# Power.net
KiCad netlist of a schematic drawn in Altium Designer
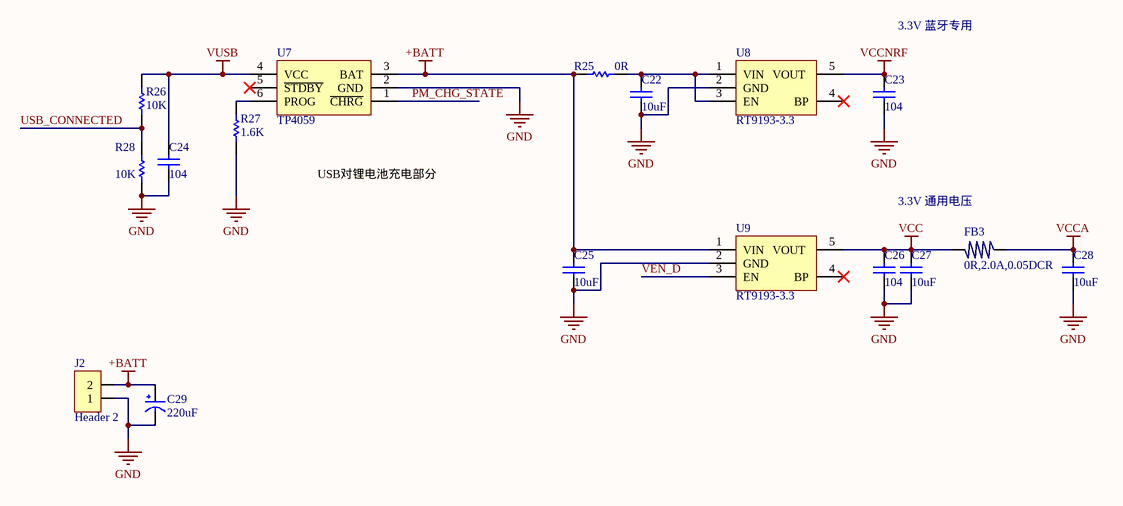
[diagram p0: Power.SchDoc]

(export (version "E")
  (design (tool "Eeschema 10.0.6"))
  (components
    (comp (ref "C22")
      (value "10uF")
      (footprint "C0603")
      (description "电容")
      (fields (field (name "PUBLISHER") "Altium Limited"))
      (libsource (lib "Devices") (part "C0603"))
    )
    (comp (ref "C23")
      (value "104")
      (footprint "C0603")
      (description "电容")
      (fields (field (name "PUBLISHER") "Altium Limited"))
      (libsource (lib "Devices") (part "C0603"))
    )
    (comp (ref "C24")
      (value "104")
      (footprint "C0603")
      (description "电容")
      (fields (field (name "PUBLISHER") "Altium Limited"))
      (libsource (lib "Devices") (part "C0603"))
    )
    (comp (ref "C25")
      (value "10uF")
      (footprint "C0603")
      (description "电容")
      (fields (field (name "PUBLISHER") "Altium Limited"))
      (libsource (lib "Devices") (part "C0603"))
    )
    (comp (ref "C26")
      (value "104")
      (footprint "C0603")
      (description "电容")
      (fields (field (name "PUBLISHER") "Altium Limited"))
      (libsource (lib "Devices") (part "C0603"))
    )
    (comp (ref "C27")
      (value "10uF")
      (footprint "C0603")
      (description "电容")
      (fields (field (name "PUBLISHER") "Altium Limited"))
      (libsource (lib "Devices") (part "C0603"))
    )
    (comp (ref "C28")
      (value "10uF")
      (footprint "C0603")
      (description "电容")
      (fields (field (name "PUBLISHER") "Altium Limited"))
      (libsource (lib "Devices") (part "C0603"))
    )
    (comp (ref "C29")
      (value "220uF")
      (footprint "TAJ-A")
      (description "极性电容")
      (libsource (lib "Devices") (part "C Pol"))
    )
    (comp (ref "FB3")
      (value "0R,2.0A,0.05DCR")
      (footprint "L0603")
      (description "磁珠")
      (libsource (lib "Devices") (part "L-Beads"))
    )
    (comp (ref "J2")
      (value "Header 2")
      (footprint "HDR1X2-2MM")
      (description "Header, 2-Pin")
      (fields (field (name "PUBLISHER") "Altium Limited"))
      (libsource (lib "Connectors") (part "Header 2"))
    )
    (comp (ref "R25")
      (value "0R")
      (footprint "R0603")
      (description "电阻")
      (fields (field (name "PUBLISHER") "Altium Limited"))
      (libsource (lib "Devices") (part "RES0603"))
    )
    (comp (ref "R26")
      (value "10K")
      (footprint "R0603")
      (description "电阻")
      (fields (field (name "PUBLISHER") "Altium Limited"))
      (libsource (lib "Devices") (part "RES0603"))
    )
    (comp (ref "R27")
      (value "1.6K")
      (footprint "R0603")
      (description "电阻")
      (fields (field (name "PUBLISHER") "Altium Limited"))
      (libsource (lib "Devices") (part "RES0603"))
    )
    (comp (ref "R28")
      (value "10K")
      (footprint "R0603")
      (description "电阻")
      (fields (field (name "PUBLISHER") "Altium Limited"))
      (libsource (lib "Devices") (part "RES0603"))
    )
    (comp (ref "U7")
      (value "TP4059")
      (footprint "SOT23-6")
      (description "锂电池充电IC")
      (libsource (lib "IC") (part "TP4059"))
    )
    (comp (ref "U8") (value "RT9193-3.3") (footprint "SOT-23-5") (libsource (lib "IC") (part "RT9193-3.3")))
    (comp (ref "U9") (value "RT9193-3.3") (footprint "SOT-23-5") (libsource (lib "IC") (part "RT9193-3.3")))
  )
  (nets
    (net (code "1") (name "+BATT") (class "Default")
      (node (ref "C25") (pin "2") (pinfunction "2_2") (pintype "passive"))
      (node (ref "C29") (pin "1") (pinfunction "VCC_1") (pintype "passive"))
      (node (ref "J2") (pin "2") (pinfunction "2_2") (pintype "passive"))
      (node (ref "R25") (pin "1") (pinfunction "1_1") (pintype "passive"))
      (node (ref "U7") (pin "3") (pinfunction "BAT_3") (pintype "passive"))
      (node (ref "U9") (pin "1") (pinfunction "VIN_1") (pintype "passive"))
    )
    (net (code "2") (name "/PM_CHG_STATE") (class "Default")
      (node (ref "U7") (pin "1") (pinfunction "~{CHRG}_1") (pintype "passive"))
    )
    (net (code "3") (name "/USB_CONNECTED") (class "Default")
      (node (ref "R26") (pin "1") (pinfunction "1_1") (pintype "passive"))
      (node (ref "R28") (pin "2") (pinfunction "2_2") (pintype "passive"))
    )
    (net (code "4") (name "/VEN_D") (class "Default")
      (node (ref "U9") (pin "3") (pinfunction "EN_3") (pintype "passive"))
    )
    (net (code "5") (name "GND") (class "Default")
      (node (ref "C22") (pin "1") (pinfunction "1_1") (pintype "passive"))
      (node (ref "C23") (pin "1") (pinfunction "1_1") (pintype "passive"))
      (node (ref "C24") (pin "1") (pinfunction "1_1") (pintype "passive"))
      (node (ref "C25") (pin "1") (pinfunction "1_1") (pintype "passive"))
      (node (ref "C26") (pin "1") (pinfunction "1_1") (pintype "passive"))
      (node (ref "C27") (pin "1") (pinfunction "1_1") (pintype "passive"))
      (node (ref "C28") (pin "1") (pinfunction "1_1") (pintype "passive"))
      (node (ref "C29") (pin "2") (pinfunction "GND_2") (pintype "passive"))
      (node (ref "J2") (pin "1") (pinfunction "1_1") (pintype "passive"))
      (node (ref "R27") (pin "1") (pinfunction "1_1") (pintype "passive"))
      (node (ref "R28") (pin "1") (pinfunction "1_1") (pintype "passive"))
      (node (ref "U7") (pin "2") (pinfunction "GND_2") (pintype "passive"))
      (node (ref "U8") (pin "2") (pinfunction "GND_2") (pintype "passive"))
      (node (ref "U9") (pin "2") (pinfunction "GND_2") (pintype "passive"))
    )
    (net (code "6") (name "Net-(U7-PROG)") (class "Default")
      (node (ref "R27") (pin "2") (pinfunction "2_2") (pintype "passive"))
      (node (ref "U7") (pin "6") (pinfunction "PROG_6") (pintype "passive"))
    )
    (net (code "7") (name "Net-(U8-EN)") (class "Default")
      (node (ref "C22") (pin "2") (pinfunction "2_2") (pintype "passive"))
      (node (ref "R25") (pin "2") (pinfunction "2_2") (pintype "passive"))
      (node (ref "U8") (pin "1") (pinfunction "VIN_1") (pintype "passive"))
      (node (ref "U8") (pin "3") (pinfunction "EN_3") (pintype "passive"))
    )
    (net (code "8") (name "VCC") (class "Default")
      (node (ref "C26") (pin "2") (pinfunction "2_2") (pintype "passive"))
      (node (ref "C27") (pin "2") (pinfunction "2_2") (pintype "passive"))
      (node (ref "FB3") (pin "2") (pintype "passive"))
      (node (ref "U9") (pin "5") (pinfunction "VOUT_5") (pintype "passive"))
    )
    (net (code "9") (name "VCCA") (class "Default")
      (node (ref "C28") (pin "2") (pinfunction "2_2") (pintype "passive"))
      (node (ref "FB3") (pin "1") (pintype "passive"))
    )
    (net (code "10") (name "VCCNRF") (class "Default")
      (node (ref "C23") (pin "2") (pinfunction "2_2") (pintype "passive"))
      (node (ref "U8") (pin "5") (pinfunction "VOUT_5") (pintype "passive"))
    )
    (net (code "11") (name "VUSB") (class "Default")
      (node (ref "C24") (pin "2") (pinfunction "2_2") (pintype "passive"))
      (node (ref "R26") (pin "2") (pinfunction "2_2") (pintype "passive"))
      (node (ref "U7") (pin "4") (pinfunction "VCC_4") (pintype "passive"))
    )
    (net (code "12") (name "unconnected-(U7-~{STDBY}-Pad5)") (class "Default")
      (node (ref "U7") (pin "5") (pinfunction "~{STDBY}_5") (pintype "passive+no_connect"))
    )
    (net (code "13") (name "unconnected-(U8-BP-Pad4)") (class "Default")
      (node (ref "U8") (pin "4") (pinfunction "BP_4") (pintype "passive+no_connect"))
    )
    (net (code "14") (name "unconnected-(U9-BP-Pad4)") (class "Default")
      (node (ref "U9") (pin "4") (pinfunction "BP_4") (pintype "passive+no_connect"))
    )
  )
)
